# Power.net
KiCad netlist of a schematic drawn in Altium Designer
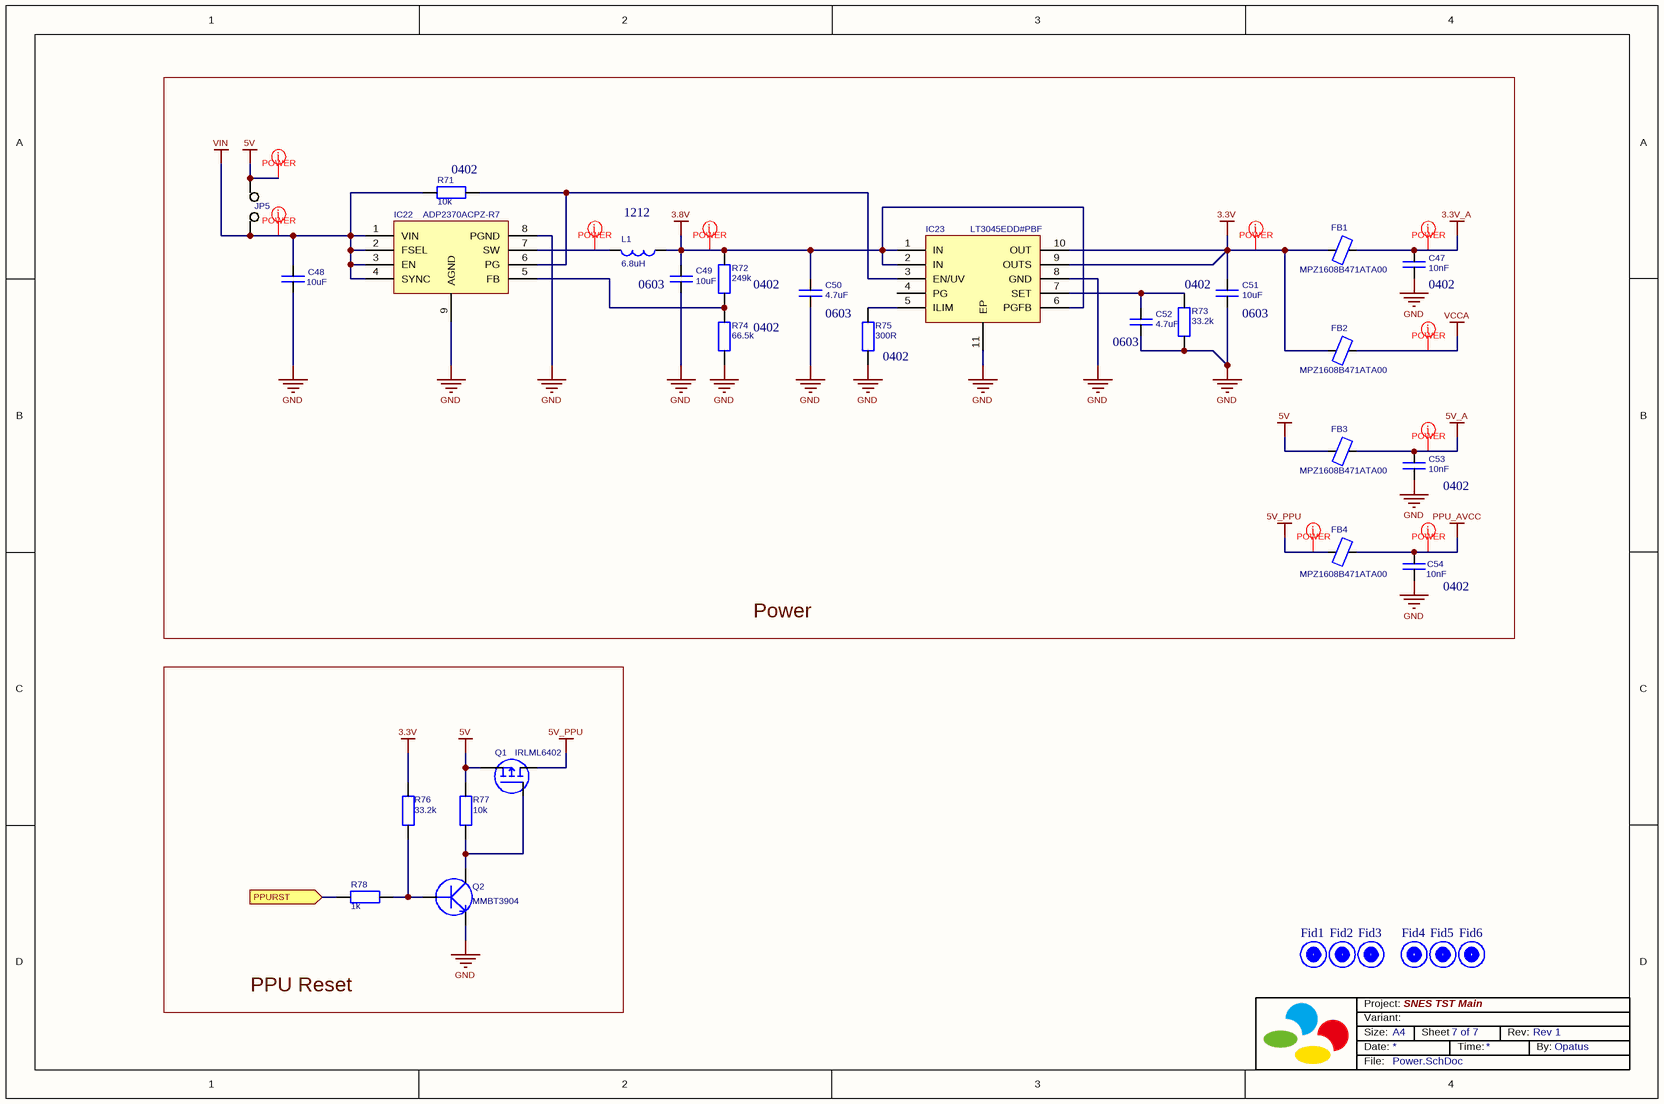
[diagram p0: Power.SchDoc]

(export (version "E")
  (design (tool "Eeschema 10.0.6"))
  (components
    (comp (ref "C47")
      (value "10nF")
      (footprint "Cap_0402_Chip")
      (fields
        (field (name "TOLERANCE") "±20%")
        (field (name "Comment") "Ceramic Capacitor 10nF 10V ±20% X7R 0402")
      )
      (libsource (lib "PCB") (part "Capacitor"))
    )
    (comp (ref "C48")
      (value "10uF")
      (footprint "Cap_0805_Chip")
      (fields
        (field (name "TOLERANCE") "±20%")
        (field (name "Comment") "Ceramic Capacitor 10uF 25V ±20% X5R 0805")
      )
      (libsource (lib "PCB") (part "Capacitor"))
    )
    (comp (ref "C49")
      (value "10uF")
      (footprint "Cap_0603_Chip")
      (fields
        (field (name "TOLERANCE") "±20%")
        (field (name "Comment") "Ceramic Capacitor 10uF 10V ±20% X5R 0603")
      )
      (libsource (lib "PCB") (part "Capacitor"))
    )
    (comp (ref "C50")
      (value "4.7uF")
      (footprint "Cap_0603_Chip")
      (fields
        (field (name "TOLERANCE") "±20%")
        (field (name "Comment") "Ceramic Capacitor 4.7uF 10V ±20% X5R 0603")
      )
      (libsource (lib "PCB") (part "Capacitor"))
    )
    (comp (ref "C51")
      (value "10uF")
      (footprint "Cap_0603_Chip")
      (fields
        (field (name "TOLERANCE") "±20%")
        (field (name "Comment") "Ceramic Capacitor 10uF 10V ±20% X5R 0603")
      )
      (libsource (lib "PCB") (part "Capacitor"))
    )
    (comp (ref "C52")
      (value "4.7uF")
      (footprint "Cap_0603_Chip")
      (fields
        (field (name "TOLERANCE") "±20%")
        (field (name "Comment") "Ceramic Capacitor 4.7uF 10V ±20% X5R 0603")
      )
      (libsource (lib "PCB") (part "Capacitor"))
    )
    (comp (ref "C53")
      (value "10nF")
      (footprint "Cap_0402_Chip")
      (fields
        (field (name "TOLERANCE") "±20%")
        (field (name "Comment") "Ceramic Capacitor 10nF 10V ±20% X7R 0402")
      )
      (libsource (lib "PCB") (part "Capacitor"))
    )
    (comp (ref "C54")
      (value "10nF")
      (footprint "Cap_0402_Chip")
      (fields
        (field (name "TOLERANCE") "±20%")
        (field (name "Comment") "Ceramic Capacitor 10nF 10V ±20% X7R 0402")
      )
      (libsource (lib "PCB") (part "Capacitor"))
    )
    (comp (ref "FB1")
      (value "470Ohm  1A")
      (footprint "Ind_0603_Chip")
      (fields
        (field (name "MANUFACTURER_PART_NUMBER") "MPZ1608B471ATA00")
        (field (name "MANUFACTURER") "TDK")
      )
      (libsource (lib "PCB") (part "Ferrite Bead"))
    )
    (comp (ref "FB2")
      (value "470Ohm  1A")
      (footprint "Ind_0603_Chip")
      (fields
        (field (name "MANUFACTURER_PART_NUMBER") "MPZ1608B471ATA00")
        (field (name "MANUFACTURER") "TDK")
      )
      (libsource (lib "PCB") (part "Ferrite Bead"))
    )
    (comp (ref "FB3")
      (value "470Ohm  1A")
      (footprint "Ind_0603_Chip")
      (fields
        (field (name "MANUFACTURER_PART_NUMBER") "MPZ1608B471ATA00")
        (field (name "MANUFACTURER") "TDK")
      )
      (libsource (lib "PCB") (part "Ferrite Bead"))
    )
    (comp (ref "FB4")
      (value "470Ohm  1A")
      (footprint "Ind_0603_Chip")
      (fields
        (field (name "MANUFACTURER_PART_NUMBER") "MPZ1608B471ATA00")
        (field (name "MANUFACTURER") "TDK")
      )
      (libsource (lib "PCB") (part "Ferrite Bead"))
    )
    (comp (ref "Fid1")
      (value "Fiducial")
      (footprint "Fiducial_1_side")
      (libsource (lib "PCB") (part "Fiducial"))
    )
    (comp (ref "Fid2")
      (value "Fiducial")
      (footprint "Fiducial_1_side")
      (libsource (lib "PCB") (part "Fiducial"))
    )
    (comp (ref "Fid3")
      (value "Fiducial")
      (footprint "Fiducial_1_side")
      (libsource (lib "PCB") (part "Fiducial"))
    )
    (comp (ref "Fid4")
      (value "Fiducial")
      (footprint "Fiducial_1_side")
      (libsource (lib "PCB") (part "Fiducial"))
    )
    (comp (ref "Fid5")
      (value "Fiducial")
      (footprint "Fiducial_1_side")
      (libsource (lib "PCB") (part "Fiducial"))
    )
    (comp (ref "Fid6")
      (value "Fiducial")
      (footprint "Fiducial_1_side")
      (libsource (lib "PCB") (part "Fiducial"))
    )
    (comp (ref "IC22")
      (value "ADP2370")
      (footprint "LFCSP8")
      (description "SMPS")
      (fields
        (field (name "MANUFACTURER") "Analog Devices Inc")
        (field (name "MANUFACTURER_PART_NUMBER") "ADP2370ACPZ-R7")
      )
      (libsource (lib "PCB") (part "ADP2370"))
    )
    (comp (ref "IC23")
      (value "LT3045")
      (footprint "DFN10")
      (description "LDO")
      (fields
        (field (name "MANUFACTURER") "Analog Devices Inc")
        (field (name "MANUFACTURER_PART_NUMBER") "LT3045EDD#PBF")
      )
      (libsource (lib "PCB") (part "LT3045"))
    )
    (comp (ref "JP5") (value "Jumper") (footprint "Jumper Big") (libsource (lib "PCB") (part "Jumper")))
    (comp (ref "L1")
      (value "6.8uH")
      (footprint "WE-MAPI_3020")
      (fields
        (field (name "MANUFACTURER") "Würth")
        (field (name "MANUFACTURER_PART_NUMBER") "74438336068")
        (field (name "Comment") "0603")
      )
      (libsource (lib "PCB") (part "L"))
    )
    (comp (ref "Q1")
      (value "IRLML6402")
      (footprint "SOT23_FET")
      (fields (field (name "MANUFACTURER") "Diodes"))
      (libsource (lib "PCB") (part "Mosfet1"))
    )
    (comp (ref "Q2")
      (value "MMBT3904")
      (footprint "SOT23_Transistor")
      (fields (field (name "MANUFACTURER") "Diodes"))
      (libsource (lib "PCB") (part "T_NPN"))
    )
    (comp (ref "R71")
      (value "10k")
      (footprint "Res_0402_Chip")
      (fields (field (name "TOLERANCE") "±1%") (field (name "Comment") "Resistor 10k 0402 ±1%"))
      (libsource (lib "") (part "R_1"))
    )
    (comp (ref "R72")
      (value "249k")
      (footprint "Res_0402_Chip")
      (fields (field (name "TOLERANCE") "±1%") (field (name "Comment") "Resistor 249k 0402 ±1%"))
      (libsource (lib "") (part "R_2"))
    )
    (comp (ref "R73")
      (value "33.2k")
      (footprint "Res_0402_Chip")
      (fields (field (name "TOLERANCE") "±1%") (field (name "Comment") "Resistor 33.2k 0402 ±1%"))
      (libsource (lib "") (part "R_2"))
    )
    (comp (ref "R74")
      (value "66.5k")
      (footprint "Res_0402_Chip")
      (fields (field (name "TOLERANCE") "±1%") (field (name "Comment") "Resistor 66.5k 0402 ±1%"))
      (libsource (lib "") (part "R_2"))
    )
    (comp (ref "R75")
      (value "300R")
      (footprint "Res_0402_Chip")
      (fields (field (name "TOLERANCE") "±1%") (field (name "Comment") "Resistor 300R 0402 ±1%"))
      (libsource (lib "") (part "R_2"))
    )
    (comp (ref "R76")
      (value "33.2k")
      (footprint "Res_0402_Chip")
      (fields (field (name "TOLERANCE") "±1%") (field (name "Comment") "Resistor 33.2k 0402 ±1%"))
      (libsource (lib "PCB") (part "R"))
    )
    (comp (ref "R77")
      (value "10k")
      (footprint "Res_0402_Chip")
      (fields (field (name "TOLERANCE") "±1%") (field (name "Comment") "Resistor 10k 0402 ±1%"))
      (libsource (lib "") (part "R_2"))
    )
    (comp (ref "R78")
      (value "1k")
      (footprint "Res_0402_Chip")
      (fields (field (name "TOLERANCE") "±1%") (field (name "Comment") "Resistor 1k 0402 ±1%"))
      (libsource (lib "") (part "R_1"))
    )
  )
  (nets
    (net (code "1") (name "/PPURST") (class "Default") (node (ref "R78") (pin "1") (pintype "passive")))
    (net (code "2") (name "3.3V") (class "Default")
      (node (ref "C51") (pin "2") (pintype "passive"))
      (node (ref "FB1") (pin "1") (pintype "passive"))
      (node (ref "FB2") (pin "1") (pintype "passive"))
      (node (ref "IC23") (pin "10") (pinfunction "OUT_10") (pintype "power_in"))
      (node (ref "IC23") (pin "9") (pinfunction "OUTS_9") (pintype "power_in"))
      (node (ref "R76") (pin "2") (pintype "passive"))
    )
    (net (code "3") (name "3.3V_A") (class "Default")
      (node (ref "C47") (pin "1") (pintype "passive"))
      (node (ref "FB1") (pin "2") (pintype "passive"))
    )
    (net (code "4") (name "3.8V") (class "Default")
      (node (ref "C49") (pin "2") (pintype "passive"))
      (node (ref "C50") (pin "2") (pintype "passive"))
      (node (ref "IC23") (pin "1") (pinfunction "IN_1") (pintype "power_in"))
      (node (ref "IC23") (pin "2") (pinfunction "IN_2") (pintype "power_in"))
      (node (ref "IC23") (pin "6") (pinfunction "PGFB_6") (pintype "power_in"))
      (node (ref "L1") (pin "2") (pintype "passive"))
      (node (ref "R72") (pin "1") (pintype "passive"))
    )
    (net (code "5") (name "5V") (class "Default")
      (node (ref "FB3") (pin "1") (pintype "passive"))
      (node (ref "JP5") (pin "1") (pinfunction "0_1") (pintype "passive"))
      (node (ref "Q1") (pin "S") (pinfunction "S_S") (pintype "passive"))
      (node (ref "R77") (pin "1") (pintype "passive"))
    )
    (net (code "6") (name "5V_A") (class "Default")
      (node (ref "C53") (pin "1") (pintype "passive"))
      (node (ref "FB3") (pin "2") (pintype "passive"))
    )
    (net (code "7") (name "5V_PPU") (class "Default")
      (node (ref "FB4") (pin "1") (pintype "passive"))
      (node (ref "Q1") (pin "D") (pinfunction "D_D") (pintype "passive"))
    )
    (net (code "8") (name "GND") (class "Default")
      (node (ref "C47") (pin "2") (pintype "passive"))
      (node (ref "C48") (pin "1") (pintype "passive"))
      (node (ref "C49") (pin "1") (pintype "passive"))
      (node (ref "C50") (pin "1") (pintype "passive"))
      (node (ref "C51") (pin "1") (pintype "passive"))
      (node (ref "C52") (pin "1") (pintype "passive"))
      (node (ref "C53") (pin "2") (pintype "passive"))
      (node (ref "C54") (pin "2") (pintype "passive"))
      (node (ref "IC22") (pin "8") (pinfunction "PGND_8") (pintype "power_in"))
      (node (ref "IC22") (pin "9") (pinfunction "AGND_9") (pintype "power_in"))
      (node (ref "IC23") (pin "11") (pinfunction "EP_11") (pintype "power_in"))
      (node (ref "IC23") (pin "8") (pinfunction "GND_8") (pintype "power_in"))
      (node (ref "Q2") (pin "E") (pinfunction "E_E") (pintype "passive"))
      (node (ref "R73") (pin "2") (pintype "passive"))
      (node (ref "R74") (pin "2") (pintype "passive"))
      (node (ref "R75") (pin "2") (pintype "passive"))
    )
    (net (code "9") (name "Net-(IC22-FB)") (class "Default")
      (node (ref "IC22") (pin "5") (pinfunction "FB_5") (pintype "power_in"))
      (node (ref "R72") (pin "2") (pintype "passive"))
      (node (ref "R74") (pin "1") (pintype "passive"))
    )
    (net (code "10") (name "Net-(IC22-PG)") (class "Default")
      (node (ref "IC22") (pin "6") (pinfunction "PG_6") (pintype "power_in"))
      (node (ref "IC23") (pin "3") (pinfunction "EN/UV_3") (pintype "power_in"))
      (node (ref "R71") (pin "2") (pintype "passive"))
    )
    (net (code "11") (name "Net-(IC22-SW)") (class "Default")
      (node (ref "IC22") (pin "7") (pinfunction "SW_7") (pintype "power_in"))
      (node (ref "L1") (pin "1") (pintype "passive"))
    )
    (net (code "12") (name "Net-(IC23-ILIM)") (class "Default")
      (node (ref "IC23") (pin "5") (pinfunction "ILIM_5") (pintype "power_in"))
      (node (ref "R75") (pin "1") (pintype "passive"))
    )
    (net (code "13") (name "Net-(IC23-SET)") (class "Default")
      (node (ref "C52") (pin "2") (pintype "passive"))
      (node (ref "IC23") (pin "7") (pinfunction "SET_7") (pintype "power_in"))
      (node (ref "R73") (pin "1") (pintype "passive"))
    )
    (net (code "14") (name "Net-(Q1-PadG)") (class "Default")
      (node (ref "Q1") (pin "G") (pinfunction "G_G") (pintype "passive"))
      (node (ref "Q2") (pin "C") (pinfunction "C_C") (pintype "passive"))
      (node (ref "R77") (pin "2") (pintype "passive"))
    )
    (net (code "15") (name "Net-(Q2-PadB)") (class "Default")
      (node (ref "Q2") (pin "B") (pinfunction "B_B") (pintype "passive"))
      (node (ref "R76") (pin "1") (pintype "passive"))
      (node (ref "R78") (pin "2") (pintype "passive"))
    )
    (net (code "16") (name "PPU_AVCC") (class "Default")
      (node (ref "C54") (pin "1") (pintype "passive"))
      (node (ref "FB4") (pin "2") (pintype "passive"))
    )
    (net (code "17") (name "VCCA") (class "Default") (node (ref "FB2") (pin "2") (pintype "passive")))
    (net (code "18") (name "VIN") (class "Default")
      (node (ref "C48") (pin "2") (pintype "passive"))
      (node (ref "IC22") (pin "1") (pinfunction "VIN_1") (pintype "power_in"))
      (node (ref "IC22") (pin "2") (pinfunction "FSEL_2") (pintype "power_in"))
      (node (ref "IC22") (pin "3") (pinfunction "EN_3") (pintype "power_in"))
      (node (ref "IC22") (pin "4") (pinfunction "SYNC_4") (pintype "power_in"))
      (node (ref "JP5") (pin "2") (pinfunction "0_2") (pintype "passive"))
      (node (ref "R71") (pin "1") (pintype "passive"))
    )
    (net (code "19") (name "unconnected-(IC23-PG-Pad4)") (class "Default")
      (node (ref "IC23") (pin "4") (pinfunction "PG_4") (pintype "power_in"))
    )
  )
)
